# PiOBD_CM4_OBD_STN2100.net
KiCad netlist of a schematic drawn in Altium Designer
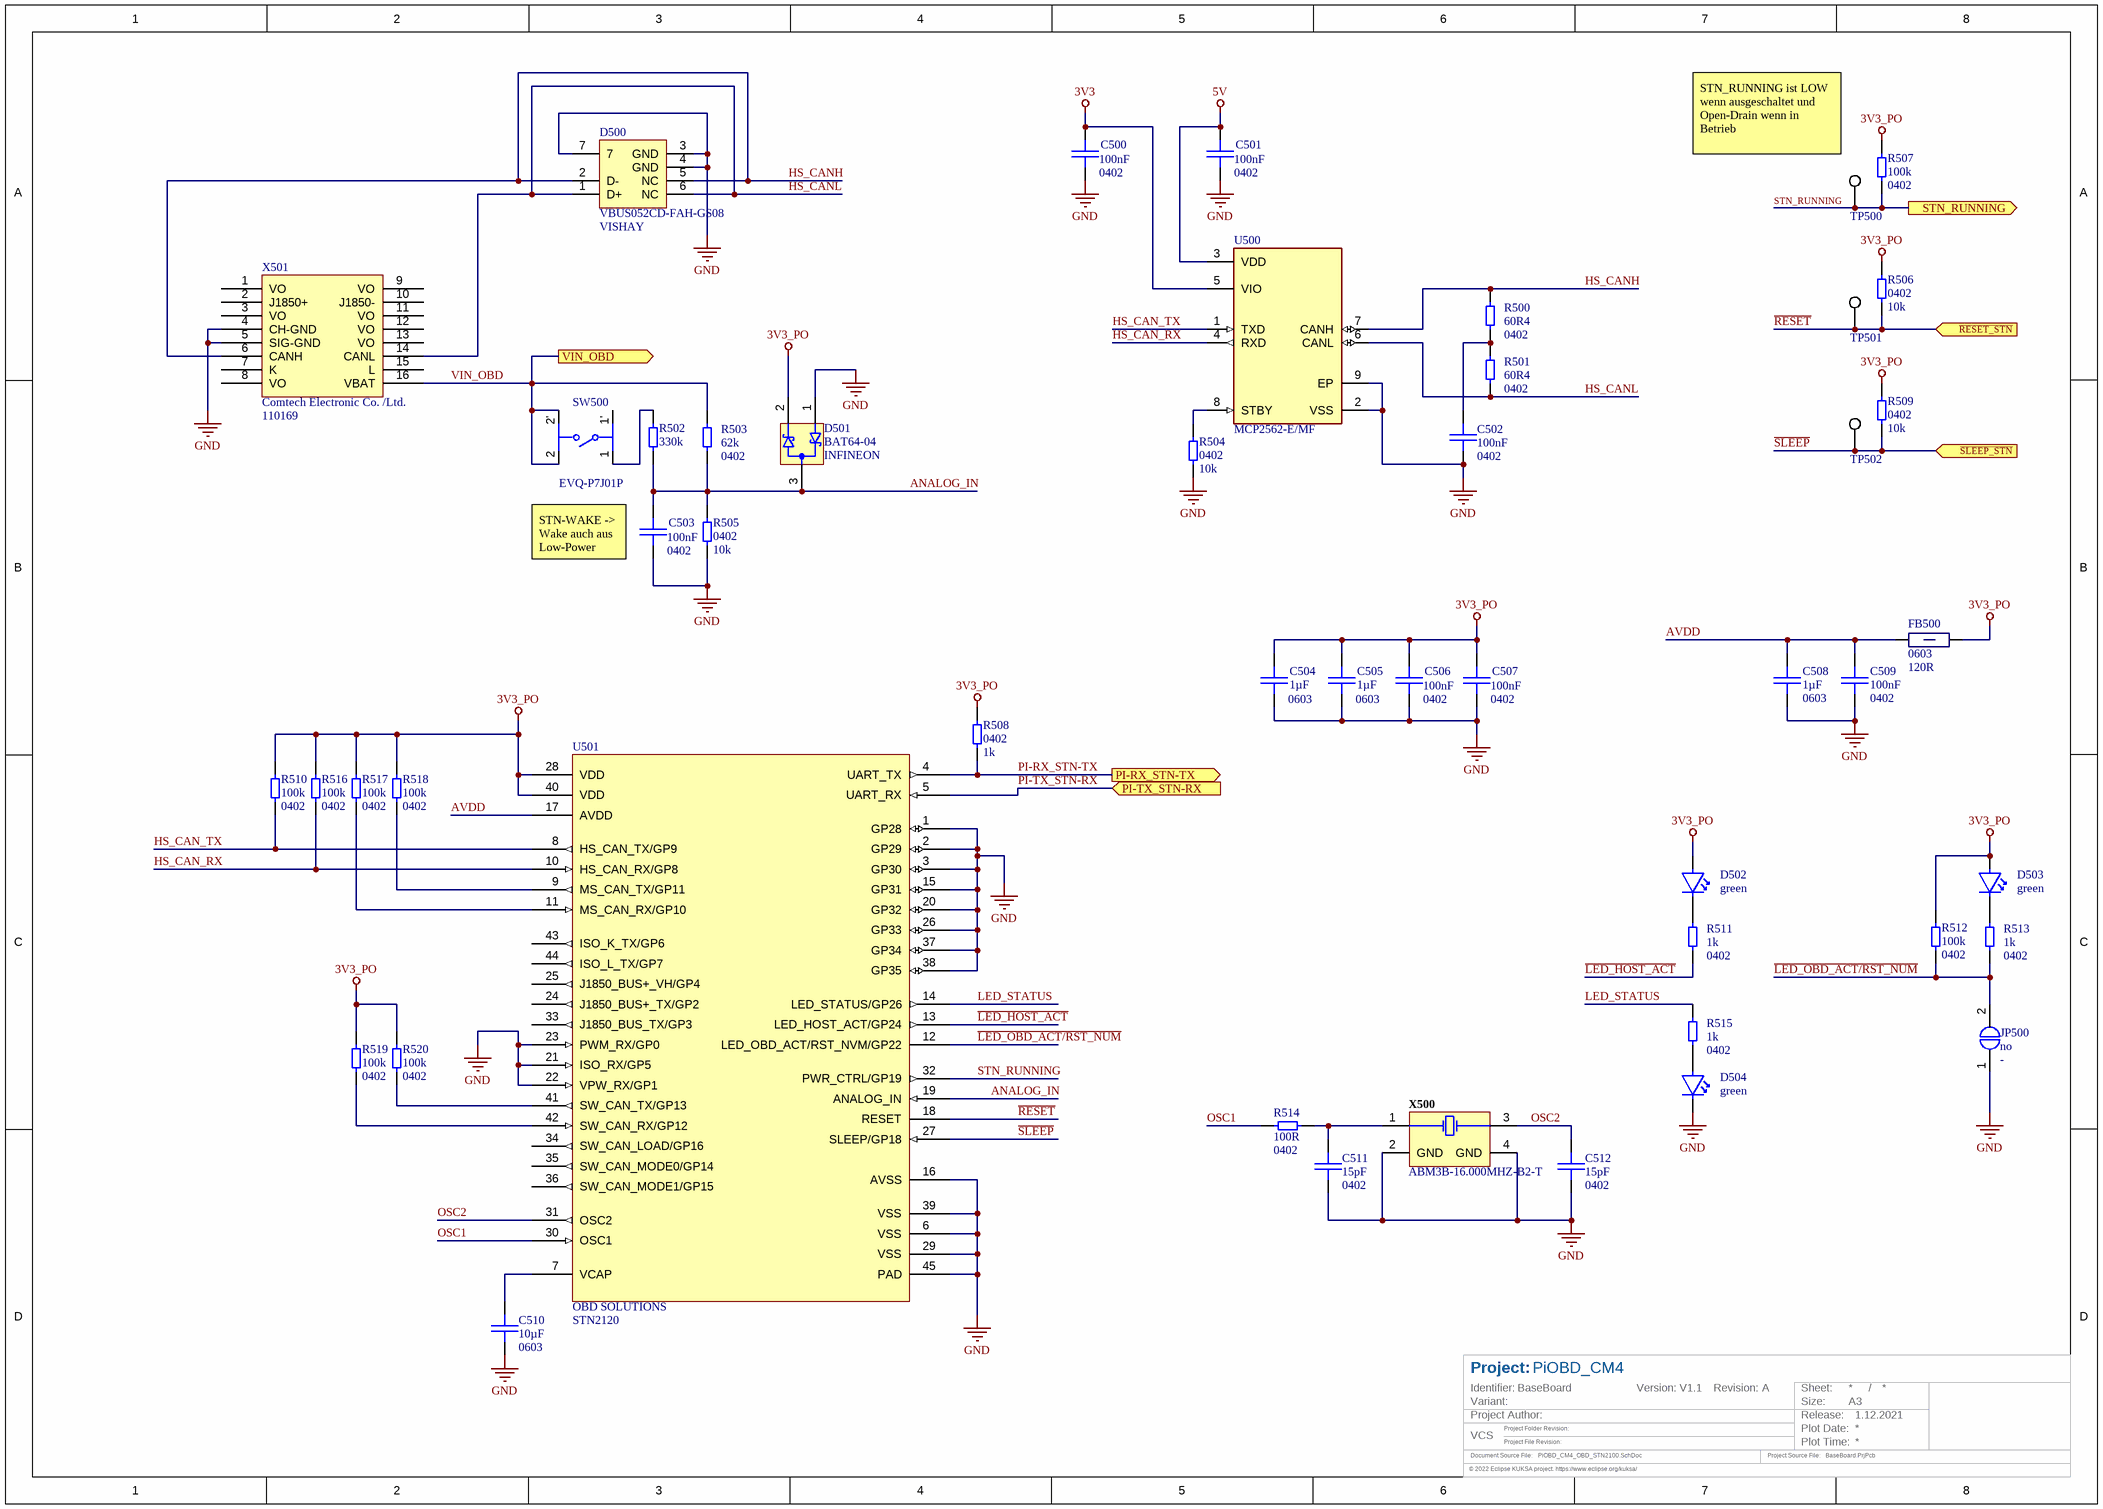
[diagram p0: PiOBD_CM4_OBD_STN2100.SchDoc]

(export (version "E")
  (design (tool "Eeschema 10.0.6"))
  (components
    (comp (ref "C500")
      (value "CAP 0402 100n -10% +10% 6.3V X7R")
      (footprint "CAP 0402 [1005 Metric] X050 N")
      (description "SMD/SMT 0402 6.3V -10% +10% X7R - Multilayer Ceramic Capacitors MLCC")
      (fields
        (field (name "MANUFACTURER") "MURATA")
        (field (name "CAPACITANCE") "100nF")
        (field (name "MANUFACTURER PART NUMBER") "GRM155R70J104KA01#")
        (field (name "CASE") "0402")
      )
      (libsource (lib "ShareLib") (part "Capacitor non-polarized - Standard Schematic"))
    )
    (comp (ref "C501")
      (value "CAP 0402 100n -10% +10% 6.3V X7R")
      (footprint "CAP 0402 [1005 Metric] X050 N")
      (description "SMD/SMT 0402 6.3V -10% +10% X7R - Multilayer Ceramic Capacitors MLCC")
      (fields
        (field (name "MANUFACTURER") "MURATA")
        (field (name "CAPACITANCE") "100nF")
        (field (name "MANUFACTURER PART NUMBER") "GRM155R70J104KA01#")
        (field (name "CASE") "0402")
      )
      (libsource (lib "ShareLib") (part "Capacitor non-polarized - Standard Schematic"))
    )
    (comp (ref "C502")
      (value "CAP 0402 100n -10% +10% 6.3V X7R")
      (footprint "CAP 0402 [1005 Metric] X050 N")
      (description "SMD/SMT 0402 6.3V -10% +10% X7R - Multilayer Ceramic Capacitors MLCC")
      (fields
        (field (name "MANUFACTURER") "MURATA")
        (field (name "CAPACITANCE") "100nF")
        (field (name "MANUFACTURER PART NUMBER") "GRM155R70J104KA01#")
        (field (name "CASE") "0402")
      )
      (libsource (lib "ShareLib") (part "Capacitor non-polarized - Standard Schematic"))
    )
    (comp (ref "C503")
      (value "CAP 0402 100n -10% +10% 6.3V X7R")
      (footprint "CAP 0402 [1005 Metric] X050 N")
      (description "SMD/SMT 0402 6.3V -10% +10% X7R - Multilayer Ceramic Capacitors MLCC")
      (fields
        (field (name "MANUFACTURER") "MURATA")
        (field (name "CAPACITANCE") "100nF")
        (field (name "MANUFACTURER PART NUMBER") "GRM155R70J104KA01#")
        (field (name "CASE") "0402")
      )
      (libsource (lib "ShareLib") (part "Capacitor non-polarized - Standard Schematic"))
    )
    (comp (ref "C504")
      (value "CAP 0603 1u -10% +10% 10V X7R")
      (footprint "CAP 0603 [1608 Metric] X080 N")
      (description "SMD/SMT 0603 10V -10% +10% X7R - Multilayer Ceramic Capacitors MLCC")
      (fields
        (field (name "CAPACITANCE") "1µF")
        (field (name "MANUFACTURER PART NUMBER") "GRM188R71A105KA61#")
        (field (name "MANUFACTURER") "MURATA")
        (field (name "CASE") "0603")
      )
      (libsource (lib "ShareLib") (part "Capacitor non-polarized - Standard Schematic"))
    )
    (comp (ref "C505")
      (value "CAP 0603 1u -10% +10% 10V X7R")
      (footprint "CAP 0603 [1608 Metric] X080 N")
      (description "SMD/SMT 0603 10V -10% +10% X7R - Multilayer Ceramic Capacitors MLCC")
      (fields
        (field (name "CAPACITANCE") "1µF")
        (field (name "MANUFACTURER PART NUMBER") "GRM188R71A105KA61#")
        (field (name "MANUFACTURER") "MURATA")
        (field (name "CASE") "0603")
      )
      (libsource (lib "ShareLib") (part "Capacitor non-polarized - Standard Schematic"))
    )
    (comp (ref "C506")
      (value "CAP 0402 100n -10% +10% 6.3V X7R")
      (footprint "CAP 0402 [1005 Metric] X050 N")
      (description "SMD/SMT 0402 6.3V -10% +10% X7R - Multilayer Ceramic Capacitors MLCC")
      (fields
        (field (name "MANUFACTURER") "MURATA")
        (field (name "CAPACITANCE") "100nF")
        (field (name "MANUFACTURER PART NUMBER") "GRM155R70J104KA01#")
        (field (name "CASE") "0402")
      )
      (libsource (lib "ShareLib") (part "Capacitor non-polarized - Standard Schematic"))
    )
    (comp (ref "C507")
      (value "CAP 0402 100n -10% +10% 6.3V X7R")
      (footprint "CAP 0402 [1005 Metric] X050 N")
      (description "SMD/SMT 0402 6.3V -10% +10% X7R - Multilayer Ceramic Capacitors MLCC")
      (fields
        (field (name "MANUFACTURER") "MURATA")
        (field (name "CAPACITANCE") "100nF")
        (field (name "MANUFACTURER PART NUMBER") "GRM155R70J104KA01#")
        (field (name "CASE") "0402")
      )
      (libsource (lib "ShareLib") (part "Capacitor non-polarized - Standard Schematic"))
    )
    (comp (ref "C508")
      (value "CAP 0603 1u -10% +10% 10V X7R")
      (footprint "CAP 0603 [1608 Metric] X080 N")
      (description "SMD/SMT 0603 10V -10% +10% X7R - Multilayer Ceramic Capacitors MLCC")
      (fields
        (field (name "CAPACITANCE") "1µF")
        (field (name "MANUFACTURER PART NUMBER") "GRM188R71A105KA61#")
        (field (name "MANUFACTURER") "MURATA")
        (field (name "CASE") "0603")
      )
      (libsource (lib "ShareLib") (part "Capacitor non-polarized - Standard Schematic"))
    )
    (comp (ref "C509")
      (value "CAP 0402 100n -10% +10% 6.3V X7R")
      (footprint "CAP 0402 [1005 Metric] X050 N")
      (description "SMD/SMT 0402 6.3V -10% +10% X7R - Multilayer Ceramic Capacitors MLCC")
      (fields
        (field (name "MANUFACTURER") "MURATA")
        (field (name "CAPACITANCE") "100nF")
        (field (name "MANUFACTURER PART NUMBER") "GRM155R70J104KA01#")
        (field (name "CASE") "0402")
      )
      (libsource (lib "ShareLib") (part "Capacitor non-polarized - Standard Schematic"))
    )
    (comp (ref "C510")
      (value "CAP 0603 10µF -20% +20% 6.3V X5R")
      (footprint "CAP 0603 [1608 Metric] X080 N")
      (description "SMT 10µF ±20% 6,3 V Keramikkondensatoren X5R")
      (fields
        (field (name "MANUFACTURER PART NUMBER") "GRM188R60J106ME84")
        (field (name "CAPACITANCE") "10µF")
        (field (name "MANUFACTURER") "MURATA")
        (field (name "CASE") "0603")
      )
      (libsource (lib "ShareLib") (part "Capacitor non-polarized - Standard Schematic"))
    )
    (comp (ref "C511")
      (value "CAP 0402 15p -2% +2% 25V C0G")
      (footprint "CAP 0402 [1005 Metric] X050 N")
      (description "SMD/SMT 0402 25V -2% +2% C0G - Multilayer Ceramic Capacitors MLCC")
      (fields
        (field (name "MANUFACTURER") "MURATA")
        (field (name "MANUFACTURER PART NUMBER") "GRM1555C1E150GA01#")
        (field (name "CASE") "0402")
        (field (name "CAPACITANCE") "15pF")
      )
      (libsource (lib "ShareLib") (part "Capacitor non-polarized - Standard Schematic"))
    )
    (comp (ref "C512")
      (value "CAP 0402 15p -2% +2% 25V C0G")
      (footprint "CAP 0402 [1005 Metric] X050 N")
      (description "SMD/SMT 0402 25V -2% +2% C0G - Multilayer Ceramic Capacitors MLCC")
      (fields
        (field (name "MANUFACTURER") "MURATA")
        (field (name "MANUFACTURER PART NUMBER") "GRM1555C1E150GA01#")
        (field (name "CASE") "0402")
        (field (name "CAPACITANCE") "15pF")
      )
      (libsource (lib "ShareLib") (part "Capacitor non-polarized - Standard Schematic"))
    )
    (comp (ref "D500")
      (value "VISHAY - VBUS052CD-FAH-GS08")
      (footprint "VISHAY - VBUS052CD-FAH")
      (description "2-Line BUS-Port ESD-Protection - Flow Through Design")
      (fields
        (field (name "MANUFACTURER PART NUMBER") "VBUS052CD-FAH-GS08")
        (field (name "MANUFACTURER") "VISHAY")
      )
      (libsource (lib "ShareLib") (part "VISHAY - VBUS052CD-FAH"))
    )
    (comp (ref "D501")
      (value "INFINEON - BAT64-04")
      (footprint "INFINEON - BAT64-04")
      (description "Dual Silicon Schottky Diodes in series configuration")
      (fields (field (name "MANUFACTURER PART NUMBER") "BAT64-04") (field (name "MANUFACTURER") "INFINEON"))
      (libsource (lib "ShareLib") (part "Dual Series Schottky Diode"))
    )
    (comp (ref "D502")
      (value "WUERTH ELEKTRONIK - 155124VS73200")
      (footprint "WUERTH ELEKTRONIK - WL-SMSW")
      (description "LED, GREEN, Right Angle SMD 3.2*1.0mm WL-SMSW SMT Mono-color Side view Waterclear")
      (fields
        (field (name "COLOUR LED1") "green")
        (field (name "MANUFACTURER") "WUERTH ELEKTRONIK")
        (field (name "MANUFACTURER PART NUMBER") "155124VS73200")
      )
      (libsource (lib "ShareLib") (part "LED - Standard Schematic"))
    )
    (comp (ref "D503")
      (value "WUERTH ELEKTRONIK - 155124VS73200")
      (footprint "WUERTH ELEKTRONIK - WL-SMSW")
      (description "LED, GREEN, Right Angle SMD 3.2*1.0mm WL-SMSW SMT Mono-color Side view Waterclear")
      (fields
        (field (name "COLOUR LED1") "green")
        (field (name "MANUFACTURER") "WUERTH ELEKTRONIK")
        (field (name "MANUFACTURER PART NUMBER") "155124VS73200")
      )
      (libsource (lib "ShareLib") (part "LED - Standard Schematic"))
    )
    (comp (ref "D504")
      (value "WUERTH ELEKTRONIK - 155124VS73200")
      (footprint "WUERTH ELEKTRONIK - WL-SMSW")
      (description "LED, GREEN, Right Angle SMD 3.2*1.0mm WL-SMSW SMT Mono-color Side view Waterclear")
      (fields
        (field (name "COLOUR LED1") "green")
        (field (name "MANUFACTURER") "WUERTH ELEKTRONIK")
        (field (name "MANUFACTURER PART NUMBER") "155124VS73200")
      )
      (libsource (lib "ShareLib") (part "LED - Standard Schematic"))
    )
    (comp (ref "FB500")
      (value "MURATA - BLM18AG121SN1D")
      (footprint "Ferrite Beads 0603 (1608 Metric)")
      (description "120 Ohms @ 100MHz 1 Power Line Ferrite Bead 0603 (1608 Metric) 800mA 180mOhm")
      (fields
        (field (name "CASE") "0603")
        (field (name "IMPEDANCE") "120R")
        (field (name "MANUFACTURER") "MURATA")
        (field (name "MANUFACTURER PART NUMBER") "BLM18AG121SN1D")
      )
      (libsource (lib "ShareLib") (part "MURATA - BLM18PG471SN1"))
    )
    (comp (ref "JP500")
      (value "Solder Jumper 0402 unbestückt")
      (footprint "Solder Jumper 0402 unbestückt")
      (fields (field (name "ASSEMBLY") "no") (field (name "CASE") "-"))
      (libsource (lib "ShareLib") (part "Solder Jumper"))
    )
    (comp (ref "R500")
      (value "RES 0402 60R4 1% 0W0625")
      (footprint "RES 0402 [1005 Metric]_N")
      (description "RC0402 series chip resistor with lead-free terminations made by thick film process")
      (fields
        (field (name "RESISTANCE") "60R4")
        (field (name "MANUFACTURER PART NUMBER") "RC0402FR-0760R4L")
        (field (name "MANUFACTURER") "YAGEO")
        (field (name "CASE") "0402")
      )
      (libsource (lib "ShareLib") (part "Standard Schematic - Resistor Universal"))
    )
    (comp (ref "R501")
      (value "RES 0402 60R4 1% 0W0625")
      (footprint "RES 0402 [1005 Metric]_N")
      (description "RC0402 series chip resistor with lead-free terminations made by thick film process")
      (fields
        (field (name "RESISTANCE") "60R4")
        (field (name "MANUFACTURER PART NUMBER") "RC0402FR-0760R4L")
        (field (name "MANUFACTURER") "YAGEO")
        (field (name "CASE") "0402")
      )
      (libsource (lib "ShareLib") (part "Standard Schematic - Resistor Universal"))
    )
    (comp (ref "R502")
      (value "RES 0402 330K 1% 0W0625")
      (footprint "RES 0402 [1005 Metric]_N")
      (description "RC0402 series chip resistor with lead-free terminations made by thick film process")
      (fields
        (field (name "MANUFACTURER PART NUMBER") "RC0402FR-07330KL")
        (field (name "MANUFACTURER") "YAGEO")
        (field (name "RESISTANCE") "330k")
      )
      (libsource (lib "ShareLib") (part "Standard Schematic - Resistor Universal"))
    )
    (comp (ref "R503")
      (value "RES 0402 62K 1% 0W0625")
      (footprint "RES 0402 [1005 Metric]_N")
      (description "RC0402 series chip resistor with lead-free terminations made by thick film process")
      (fields
        (field (name "MANUFACTURER PART NUMBER") "RC0402FR-0762KL")
        (field (name "RESISTANCE") "62k")
        (field (name "MANUFACTURER") "YAGEO")
        (field (name "CASE") "0402")
      )
      (libsource (lib "ShareLib") (part "Standard Schematic - Resistor Universal"))
    )
    (comp (ref "R504")
      (value "RES 0402 10K 1% 0W0625")
      (footprint "RES 0402 [1005 Metric]_N")
      (description "RC0402 series chip resistor with lead-free terminations made by thick film process")
      (fields
        (field (name "MANUFACTURER PART NUMBER") "RC0402FR-0710KL")
        (field (name "CASE") "0402")
        (field (name "MANUFACTURER") "YAGEO")
        (field (name "RESISTANCE") "10k")
      )
      (libsource (lib "ShareLib") (part "Standard Schematic - Resistor Universal"))
    )
    (comp (ref "R505")
      (value "RES 0402 10K 1% 0W0625")
      (footprint "RES 0402 [1005 Metric]_N")
      (description "RC0402 series chip resistor with lead-free terminations made by thick film process")
      (fields
        (field (name "MANUFACTURER PART NUMBER") "RC0402FR-0710KL")
        (field (name "CASE") "0402")
        (field (name "MANUFACTURER") "YAGEO")
        (field (name "RESISTANCE") "10k")
      )
      (libsource (lib "ShareLib") (part "Standard Schematic - Resistor Universal"))
    )
    (comp (ref "R506")
      (value "RES 0402 10K 1% 0W0625")
      (footprint "RES 0402 [1005 Metric]_N")
      (description "RC0402 series chip resistor with lead-free terminations made by thick film process")
      (fields
        (field (name "MANUFACTURER PART NUMBER") "RC0402FR-0710KL")
        (field (name "CASE") "0402")
        (field (name "MANUFACTURER") "YAGEO")
        (field (name "RESISTANCE") "10k")
      )
      (libsource (lib "ShareLib") (part "Standard Schematic - Resistor Universal"))
    )
    (comp (ref "R507")
      (value "RES 0402 100K 1% 0W0625")
      (footprint "RES 0402 [1005 Metric]_N")
      (description "RC0402 series chip resistor with lead-free terminations made by thick film process")
      (fields
        (field (name "RESISTANCE") "100k")
        (field (name "MANUFACTURER PART NUMBER") "RC0402FR-07100KL")
        (field (name "CASE") "0402")
        (field (name "MANUFACTURER") "YAGEO")
      )
      (libsource (lib "ShareLib") (part "Standard Schematic - Resistor Universal"))
    )
    (comp (ref "R508")
      (value "RES 0402 1K 1% 0W0625")
      (footprint "RES 0402 [1005 Metric]_N")
      (description "RC0402 series chip resistor with lead-free terminations made by thick film process")
      (fields
        (field (name "CASE") "0402")
        (field (name "MANUFACTURER PART NUMBER") "RC0402FR-071KL")
        (field (name "MANUFACTURER") "YAGEO")
        (field (name "RESISTANCE") "1k")
      )
      (libsource (lib "ShareLib") (part "Standard Schematic - Resistor Universal"))
    )
    (comp (ref "R509")
      (value "RES 0402 10K 1% 0W0625")
      (footprint "RES 0402 [1005 Metric]_N")
      (description "RC0402 series chip resistor with lead-free terminations made by thick film process")
      (fields
        (field (name "MANUFACTURER PART NUMBER") "RC0402FR-0710KL")
        (field (name "CASE") "0402")
        (field (name "MANUFACTURER") "YAGEO")
        (field (name "RESISTANCE") "10k")
      )
      (libsource (lib "ShareLib") (part "Standard Schematic - Resistor Universal"))
    )
    (comp (ref "R510")
      (value "RES 0402 100K 1% 0W0625")
      (footprint "RES 0402 [1005 Metric]_N")
      (description "RC0402 series chip resistor with lead-free terminations made by thick film process")
      (fields
        (field (name "RESISTANCE") "100k")
        (field (name "MANUFACTURER PART NUMBER") "RC0402FR-07100KL")
        (field (name "CASE") "0402")
        (field (name "MANUFACTURER") "YAGEO")
      )
      (libsource (lib "ShareLib") (part "Standard Schematic - Resistor Universal"))
    )
    (comp (ref "R511")
      (value "RES 0402 1K 1% 0W0625")
      (footprint "RES 0402 [1005 Metric]_N")
      (description "RC0402 series chip resistor with lead-free terminations made by thick film process")
      (fields
        (field (name "CASE") "0402")
        (field (name "MANUFACTURER PART NUMBER") "RC0402FR-071KL")
        (field (name "MANUFACTURER") "YAGEO")
        (field (name "RESISTANCE") "1k")
      )
      (libsource (lib "ShareLib") (part "Standard Schematic - Resistor Universal"))
    )
    (comp (ref "R512")
      (value "RES 0402 100K 1% 0W0625")
      (footprint "RES 0402 [1005 Metric]_N")
      (description "RC0402 series chip resistor with lead-free terminations made by thick film process")
      (fields
        (field (name "RESISTANCE") "100k")
        (field (name "MANUFACTURER PART NUMBER") "RC0402FR-07100KL")
        (field (name "CASE") "0402")
        (field (name "MANUFACTURER") "YAGEO")
      )
      (libsource (lib "ShareLib") (part "Standard Schematic - Resistor Universal"))
    )
    (comp (ref "R513")
      (value "RES 0402 1K 1% 0W0625")
      (footprint "RES 0402 [1005 Metric]_N")
      (description "RC0402 series chip resistor with lead-free terminations made by thick film process")
      (fields
        (field (name "CASE") "0402")
        (field (name "MANUFACTURER PART NUMBER") "RC0402FR-071KL")
        (field (name "MANUFACTURER") "YAGEO")
        (field (name "RESISTANCE") "1k")
      )
      (libsource (lib "ShareLib") (part "Standard Schematic - Resistor Universal"))
    )
    (comp (ref "R514")
      (value "RES 0402 100R 1% 63mW")
      (footprint "RES 0402 [1005 Metric]_N")
      (description "RC0402 series chip resistor with lead-free terminations made by thick film process")
      (fields
        (field (name "RESISTANCE") "100R")
        (field (name "CASE") "0402")
        (field (name "MANUFACTURER") "ROHM")
        (field (name "MANUFACTURER PART NUMBER") "MCR01MZPF100")
      )
      (libsource (lib "ShareLib") (part "Standard Schematic - Resistor Universal"))
    )
    (comp (ref "R515")
      (value "RES 0402 1K 1% 0W0625")
      (footprint "RES 0402 [1005 Metric]_N")
      (description "RC0402 series chip resistor with lead-free terminations made by thick film process")
      (fields
        (field (name "CASE") "0402")
        (field (name "MANUFACTURER PART NUMBER") "RC0402FR-071KL")
        (field (name "MANUFACTURER") "YAGEO")
        (field (name "RESISTANCE") "1k")
      )
      (libsource (lib "ShareLib") (part "Standard Schematic - Resistor Universal"))
    )
    (comp (ref "R516")
      (value "RES 0402 100K 1% 0W0625")
      (footprint "RES 0402 [1005 Metric]_N")
      (description "RC0402 series chip resistor with lead-free terminations made by thick film process")
      (fields
        (field (name "RESISTANCE") "100k")
        (field (name "MANUFACTURER PART NUMBER") "RC0402FR-07100KL")
        (field (name "CASE") "0402")
        (field (name "MANUFACTURER") "YAGEO")
      )
      (libsource (lib "ShareLib") (part "Standard Schematic - Resistor Universal"))
    )
    (comp (ref "R517")
      (value "RES 0402 100K 1% 0W0625")
      (footprint "RES 0402 [1005 Metric]_N")
      (description "RC0402 series chip resistor with lead-free terminations made by thick film process")
      (fields
        (field (name "RESISTANCE") "100k")
        (field (name "MANUFACTURER PART NUMBER") "RC0402FR-07100KL")
        (field (name "CASE") "0402")
        (field (name "MANUFACTURER") "YAGEO")
      )
      (libsource (lib "ShareLib") (part "Standard Schematic - Resistor Universal"))
    )
    (comp (ref "R518")
      (value "RES 0402 100K 1% 0W0625")
      (footprint "RES 0402 [1005 Metric]_N")
      (description "RC0402 series chip resistor with lead-free terminations made by thick film process")
      (fields
        (field (name "RESISTANCE") "100k")
        (field (name "MANUFACTURER PART NUMBER") "RC0402FR-07100KL")
        (field (name "CASE") "0402")
        (field (name "MANUFACTURER") "YAGEO")
      )
      (libsource (lib "ShareLib") (part "Standard Schematic - Resistor Universal"))
    )
    (comp (ref "R519")
      (value "RES 0402 100K 1% 0W0625")
      (footprint "RES 0402 [1005 Metric]_N")
      (description "RC0402 series chip resistor with lead-free terminations made by thick film process")
      (fields
        (field (name "RESISTANCE") "100k")
        (field (name "MANUFACTURER PART NUMBER") "RC0402FR-07100KL")
        (field (name "CASE") "0402")
        (field (name "MANUFACTURER") "YAGEO")
      )
      (libsource (lib "ShareLib") (part "Standard Schematic - Resistor Universal"))
    )
    (comp (ref "R520")
      (value "RES 0402 100K 1% 0W0625")
      (footprint "RES 0402 [1005 Metric]_N")
      (description "RC0402 series chip resistor with lead-free terminations made by thick film process")
      (fields
        (field (name "RESISTANCE") "100k")
        (field (name "MANUFACTURER PART NUMBER") "RC0402FR-07100KL")
        (field (name "CASE") "0402")
        (field (name "MANUFACTURER") "YAGEO")
      )
      (libsource (lib "ShareLib") (part "Standard Schematic - Resistor Universal"))
    )
    (comp (ref "SW500")
      (value "EVQ-P7J01P")
      (footprint "FP-EVQ-P7J01P-MFG")
      (description "SWITCH TACTILE SPST-NO 0.05A 12V")
      (fields
        (field (name "MANUFACTURER") "Panasonic")
        (field (name "OCTOPART") "https://octopart.com/evq-p7j01p-panasonic-29917078")
      )
      (libsource (lib "Altium Content Vault") (part "81ddb76e3b1ae09a591072546e26dfd"))
    )
    (comp (ref "TP500")
      (value "Testpad, 0.8mm x 0.8mm, round")
      (footprint "Testpad, 0.8mm x 0.8mm, round")
      (libsource (lib "ShareLib") (part "Testpoint (No BOM)"))
    )
    (comp (ref "TP501")
      (value "Testpad, 0.8mm x 0.8mm, round")
      (footprint "Testpad, 0.8mm x 0.8mm, round")
      (libsource (lib "ShareLib") (part "Testpoint (No BOM)"))
    )
    (comp (ref "TP502")
      (value "Testpad, 0.8mm x 0.8mm, round")
      (footprint "Testpad, 0.8mm x 0.8mm, round")
      (libsource (lib "ShareLib") (part "Testpoint (No BOM)"))
    )
    (comp (ref "U500")
      (value "MCP2562-E/MF")
      (footprint "FP-C04-062-MFG")
      (description "IC TRANSCEIVER HALF 1/1 8DFN")
      (fields
        (field (name "OCTOPART") "https://octopart.com/mcp2562-e%2Fmf-microchip-28494619")
        (field (name "MANUFACTURER") "Microchip Technology")
      )
      (libsource (lib "Altium Content Vault") (part "02f17a9452f5565b4e0dbded7188508"))
    )
    (comp (ref "U501")
      (value "OBD SOLUTIONS - STN2120")
      (footprint "QFN65P800X800X100_HS-45N")
      (fields
        (field (name "MANUFACTURER") "OBD SOLUTIONS")
        (field (name "MANUFACTURER PART NUMBER") "STN2120")
      )
      (libsource (lib "ShareLib") (part "STN2120"))
    )
    (comp (ref "X500")
      (value "ABM3B-16.000MHZ-B2-T")
      (footprint "ABRA-ABM3B-4_V")
      (description "Ceramic SMD Crystal, 16 MHz, +/- 20 ppm, 50 Ohm, -20 to 70 degC, 4-Pin SMD, RoHS, Tape and Reel")
      (fields (field (name "TOLERANCE") "30%"))
      (libsource (lib "Altium Content Vault") (part "XTAL-1-3-4"))
    )
    (comp (ref "X501")
      (value "COMTECH ELECTRONIC - OBD-2 Stiftblock")
      (footprint "COMTECH ELECTRONIC - OBD-2 Stiftblock-Footprint-1")
      (description "OBD-2 Stiftblock männlich PCB TH PKW Typ A")
      (fields
        (field (name "MANUFACTURER") "Comtech Electronic Co. /Ltd.")
        (field (name "MANUFACTURER PART NUMBER") "110169")
      )
      (libsource (lib "ShareLib") (part "COMTECH ELECTRONIC - OBD-2 Stiftblock"))
    )
  )
  (nets
    (net (code "1") (name "/ANALOG_IN") (class "Default")
      (node (ref "C503") (pin "2") (pinfunction "2_2") (pintype "passive"))
      (node (ref "D501") (pin "3") (pinfunction "3_3") (pintype "passive"))
      (node (ref "R502") (pin "1") (pinfunction "1_1") (pintype "passive"))
      (node (ref "R503") (pin "1") (pinfunction "1_1") (pintype "passive"))
      (node (ref "R505") (pin "1") (pinfunction "1_1") (pintype "passive"))
      (node (ref "U501") (pin "19") (pinfunction "ANALOG_IN_19") (pintype "input"))
    )
    (net (code "2") (name "/AVDD") (class "Default")
      (node (ref "C508") (pin "1") (pinfunction "1_1") (pintype "passive"))
      (node (ref "C509") (pin "2") (pinfunction "2_2") (pintype "passive"))
      (node (ref "FB500") (pin "2") (pinfunction "2_2") (pintype "passive"))
      (node (ref "U501") (pin "17") (pinfunction "AVDD_17") (pintype "passive"))
    )
    (net (code "3") (name "/HS_CANH") (class "Default")
      (node (ref "D500") (pin "2") (pinfunction "D-_2") (pintype "passive"))
      (node (ref "D500") (pin "5") (pinfunction "NC_5") (pintype "passive"))
      (node (ref "R500") (pin "2") (pinfunction "2_2") (pintype "passive"))
      (node (ref "U500") (pin "7") (pinfunction "CANH_7") (pintype "bidirectional"))
      (node (ref "X501") (pin "6") (pinfunction "CANH_6") (pintype "passive"))
    )
    (net (code "4") (name "/HS_CANL") (class "Default")
      (node (ref "D500") (pin "1") (pinfunction "D+_1") (pintype "passive"))
      (node (ref "D500") (pin "6") (pinfunction "NC_6") (pintype "passive"))
      (node (ref "R501") (pin "1") (pinfunction "1_1") (pintype "passive"))
      (node (ref "U500") (pin "6") (pinfunction "CANL_6") (pintype "bidirectional"))
      (node (ref "X501") (pin "14") (pinfunction "CANL_14") (pintype "passive"))
    )
    (net (code "5") (name "/HS_CAN_RX") (class "Default")
      (node (ref "R516") (pin "1") (pinfunction "1_1") (pintype "passive"))
      (node (ref "U500") (pin "4") (pinfunction "RXD_4") (pintype "output"))
      (node (ref "U501") (pin "10") (pinfunction "HS_CAN_RX/GP8_10") (pintype "input"))
    )
    (net (code "6") (name "/HS_CAN_TX") (class "Default")
      (node (ref "R510") (pin "1") (pinfunction "1_1") (pintype "passive"))
      (node (ref "U500") (pin "1") (pinfunction "TXD_1") (pintype "input"))
      (node (ref "U501") (pin "8") (pinfunction "HS_CAN_TX/GP9_8") (pintype "output"))
    )
    (net (code "7") (name "/LED_HOST_ACT") (class "Default")
      (node (ref "R511") (pin "1") (pinfunction "1_1") (pintype "passive"))
      (node (ref "U501") (pin "13") (pinfunction "LED_HOST_ACT/GP24_13") (pintype "output"))
    )
    (net (code "8") (name "/LED_OBD_ACT{slash}RST_NUM") (class "Default")
      (node (ref "JP500") (pin "2") (pinfunction "2_2") (pintype "passive"))
      (node (ref "R512") (pin "1") (pinfunction "1_1") (pintype "passive"))
      (node (ref "R513") (pin "1") (pinfunction "1_1") (pintype "passive"))
      (node (ref "U501") (pin "12") (pinfunction "LED_OBD_ACT/RST_NVM/GP22_12") (pintype "passive"))
    )
    (net (code "9") (name "/LED_STATUS") (class "Default")
      (node (ref "R515") (pin "2") (pinfunction "2_2") (pintype "passive"))
      (node (ref "U501") (pin "14") (pinfunction "LED_STATUS/GP26_14") (pintype "output"))
    )
    (net (code "10") (name "/OSC1") (class "Default")
      (node (ref "R514") (pin "1") (pinfunction "1_1") (pintype "passive"))
      (node (ref "U501") (pin "30") (pinfunction "OSC1_30") (pintype "input"))
    )
    (net (code "11") (name "/OSC2") (class "Default")
      (node (ref "C512") (pin "2") (pinfunction "2_2") (pintype "passive"))
      (node (ref "U501") (pin "31") (pinfunction "OSC2_31") (pintype "output"))
      (node (ref "X500") (pin "3") (pinfunction "X2_3") (pintype "passive"))
    )
    (net (code "12") (name "/PI-RX_STN-TX") (class "Default")
      (node (ref "R508") (pin "1") (pinfunction "1_1") (pintype "passive"))
      (node (ref "U501") (pin "4") (pinfunction "UART_TX_4") (pintype "output"))
    )
    (net (code "13") (name "/PI-TX_STN-RX") (class "Default")
      (node (ref "U501") (pin "5") (pinfunction "UART_RX_5") (pintype "input"))
    )
    (net (code "14") (name "/RESET") (class "Default")
      (node (ref "R506") (pin "2") (pinfunction "2_2") (pintype "passive"))
      (node (ref "TP501") (pin "1") (pinfunction "1_1") (pintype "passive"))
      (node (ref "U501") (pin "18") (pinfunction "RESET_18") (pintype "passive"))
    )
    (net (code "15") (name "/SLEEP") (class "Default")
      (node (ref "R509") (pin "2") (pinfunction "2_2") (pintype "passive"))
      (node (ref "TP502") (pin "1") (pinfunction "1_1") (pintype "passive"))
      (node (ref "U501") (pin "27") (pinfunction "SLEEP/GP18_27") (pintype "input"))
    )
    (net (code "16") (name "/STN_RUNNING") (class "Default")
      (node (ref "R507") (pin "1") (pinfunction "1_1") (pintype "passive"))
      (node (ref "TP500") (pin "1") (pinfunction "1_1") (pintype "passive"))
      (node (ref "U501") (pin "32") (pinfunction "PWR_CTRL/GP19_32") (pintype "output"))
    )
    (net (code "17") (name "/VIN_OBD") (class "Default")
      (node (ref "R503") (pin "2") (pinfunction "2_2") (pintype "passive"))
      (node (ref "SW500") (pin "2") (pinfunction "2_2") (pintype "passive"))
      (node (ref "SW500") (pin "2'") (pinfunction "2'_2'") (pintype "passive"))
      (node (ref "X501") (pin "16") (pinfunction "VBAT_16") (pintype "passive"))
    )
    (net (code "18") (name "3V3") (class "Default")
      (node (ref "C500") (pin "2") (pinfunction "2_2") (pintype "passive"))
      (node (ref "U500") (pin "5") (pinfunction "VIO_5") (pintype "power_in"))
    )
    (net (code "19") (name "3V3_PO") (class "Default")
      (node (ref "C504") (pin "1") (pinfunction "1_1") (pintype "passive"))
      (node (ref "C505") (pin "1") (pinfunction "1_1") (pintype "passive"))
      (node (ref "C506") (pin "2") (pinfunction "2_2") (pintype "passive"))
      (node (ref "C507") (pin "2") (pinfunction "2_2") (pintype "passive"))
      (node (ref "D501") (pin "2") (pinfunction "2_2") (pintype "passive"))
      (node (ref "D502") (pin "A") (pinfunction "A_A") (pintype "passive"))
      (node (ref "D503") (pin "A") (pinfunction "A_A") (pintype "passive"))
      (node (ref "FB500") (pin "1") (pinfunction "1_1") (pintype "passive"))
      (node (ref "R506") (pin "1") (pinfunction "1_1") (pintype "passive"))
      (node (ref "R507") (pin "2") (pinfunction "2_2") (pintype "passive"))
      (node (ref "R508") (pin "2") (pinfunction "2_2") (pintype "passive"))
      (node (ref "R509") (pin "1") (pinfunction "1_1") (pintype "passive"))
      (node (ref "R510") (pin "2") (pinfunction "2_2") (pintype "passive"))
      (node (ref "R512") (pin "2") (pinfunction "2_2") (pintype "passive"))
      (node (ref "R516") (pin "2") (pinfunction "2_2") (pintype "passive"))
      (node (ref "R517") (pin "2") (pinfunction "2_2") (pintype "passive"))
      (node (ref "R518") (pin "2") (pinfunction "2_2") (pintype "passive"))
      (node (ref "R519") (pin "2") (pinfunction "2_2") (pintype "passive"))
      (node (ref "R520") (pin "2") (pinfunction "2_2") (pintype "passive"))
      (node (ref "U501") (pin "28") (pinfunction "VDD_28") (pintype "passive"))
      (node (ref "U501") (pin "40") (pinfunction "VDD_40") (pintype "passive"))
    )
    (net (code "20") (name "5V") (class "Default")
      (node (ref "C501") (pin "2") (pinfunction "2_2") (pintype "passive"))
      (node (ref "U500") (pin "3") (pinfunction "VDD_3") (pintype "power_in"))
    )
    (net (code "21") (name "GND") (class "Default")
      (node (ref "C500") (pin "1") (pinfunction "1_1") (pintype "passive"))
      (node (ref "C501") (pin "1") (pinfunction "1_1") (pintype "passive"))
      (node (ref "C502") (pin "2") (pinfunction "2_2") (pintype "passive"))
      (node (ref "C503") (pin "1") (pinfunction "1_1") (pintype "passive"))
      (node (ref "C504") (pin "2") (pinfunction "2_2") (pintype "passive"))
      (node (ref "C505") (pin "2") (pinfunction "2_2") (pintype "passive"))
      (node (ref "C506") (pin "1") (pinfunction "1_1") (pintype "passive"))
      (node (ref "C507") (pin "1") (pinfunction "1_1") (pintype "passive"))
      (node (ref "C508") (pin "2") (pinfunction "2_2") (pintype "passive"))
      (node (ref "C509") (pin "1") (pinfunction "1_1") (pintype "passive"))
      (node (ref "C510") (pin "2") (pinfunction "2_2") (pintype "passive"))
      (node (ref "C511") (pin "1") (pinfunction "1_1") (pintype "passive"))
      (node (ref "C512") (pin "1") (pinfunction "1_1") (pintype "passive"))
      (node (ref "D500") (pin "3") (pinfunction "GND_3") (pintype "power_in"))
      (node (ref "D500") (pin "4") (pinfunction "GND_4") (pintype "power_in"))
      (node (ref "D500") (pin "7") (pinfunction "7_7") (pintype "passive"))
      (node (ref "D501") (pin "1") (pinfunction "1_1") (pintype "passive"))
      (node (ref "D504") (pin "C") (pinfunction "C_C") (pintype "passive"))
      (node (ref "JP500") (pin "1") (pinfunction "1_1") (pintype "passive"))
      (node (ref "R504") (pin "2") (pinfunction "2_2") (pintype "passive"))
      (node (ref "R505") (pin "2") (pinfunction "2_2") (pintype "passive"))
      (node (ref "U500") (pin "2") (pinfunction "VSS_2") (pintype "power_in"))
      (node (ref "U500") (pin "9") (pinfunction "EP_9") (pintype "power_in"))
      (node (ref "U501") (pin "1") (pinfunction "GP28_1") (pintype "bidirectional"))
      (node (ref "U501") (pin "15") (pinfunction "GP31_15") (pintype "bidirectional"))
      (node (ref "U501") (pin "16") (pinfunction "AVSS_16") (pintype "passive"))
      (node (ref "U501") (pin "2") (pinfunction "GP29_2") (pintype "bidirectional"))
      (node (ref "U501") (pin "20") (pinfunction "GP32_20") (pintype "bidirectional"))
      (node (ref "U501") (pin "21") (pinfunction "ISO_RX/GP5_21") (pintype "input"))
      (node (ref "U501") (pin "22") (pinfunction "VPW_RX/GP1_22") (pintype "input"))
      (node (ref "U501") (pin "23") (pinfunction "PWM_RX/GP0_23") (pintype "input"))
      (node (ref "U501") (pin "26") (pinfunction "GP33_26") (pintype "bidirectional"))
      (node (ref "U501") (pin "29") (pinfunction "VSS_29") (pintype "passive"))
      (node (ref "U501") (pin "3") (pinfunction "GP30_3") (pintype "bidirectional"))
      (node (ref "U501") (pin "37") (pinfunction "GP34_37") (pintype "bidirectional"))
      (node (ref "U501") (pin "38") (pinfunction "GP35_38") (pintype "bidirectional"))
      (node (ref "U501") (pin "39") (pinfunction "VSS_39") (pintype "passive"))
      (node (ref "U501") (pin "45") (pinfunction "PAD_45") (pintype "passive"))
      (node (ref "U501") (pin "6") (pinfunction "VSS_6") (pintype "passive"))
      (node (ref "X500") (pin "2") (pinfunction "GND_2") (pintype "power_in"))
      (node (ref "X500") (pin "4") (pinfunction "GND_4") (pintype "power_in"))
      (node (ref "X501") (pin "4") (pinfunction "CH-GND_4") (pintype "passive"))
      (node (ref "X501") (pin "5") (pinfunction "SIG-GND_5") (pintype "passive"))
    )
    (net (code "22") (name "Net-(C502-Pad1)") (class "Default")
      (node (ref "C502") (pin "1") (pinfunction "1_1") (pintype "passive"))
      (node (ref "R500") (pin "1") (pinfunction "1_1") (pintype "passive"))
      (node (ref "R501") (pin "2") (pinfunction "2_2") (pintype "passive"))
    )
    (net (code "23") (name "Net-(D502-PadC)") (class "Default")
      (node (ref "D502") (pin "C") (pinfunction "C_C") (pintype "passive"))
      (node (ref "R511") (pin "2") (pinfunction "2_2") (pintype "passive"))
    )
    (net (code "24") (name "Net-(D503-PadC)") (class "Default")
      (node (ref "D503") (pin "C") (pinfunction "C_C") (pintype "passive"))
      (node (ref "R513") (pin "2") (pinfunction "2_2") (pintype "passive"))
    )
    (net (code "25") (name "Net-(D504-PadA)") (class "Default")
      (node (ref "D504") (pin "A") (pinfunction "A_A") (pintype "passive"))
      (node (ref "R515") (pin "1") (pinfunction "1_1") (pintype "passive"))
    )
    (net (code "26") (name "Net-(R502-Pad2)") (class "Default")
      (node (ref "R502") (pin "2") (pinfunction "2_2") (pintype "passive"))
      (node (ref "SW500") (pin "1") (pinfunction "1_1") (pintype "passive"))
    )
    (net (code "27") (name "Net-(U500-STBY)") (class "Default")
      (node (ref "R504") (pin "1") (pinfunction "1_1") (pintype "passive"))
      (node (ref "U500") (pin "8") (pinfunction "STBY_8") (pintype "input"))
    )
    (net (code "28") (name "Net-(U501-MS_CAN_RX{slash}GP10)") (class "Default")
      (node (ref "R517") (pin "1") (pinfunction "1_1") (pintype "passive"))
      (node (ref "U501") (pin "11") (pinfunction "MS_CAN_RX/GP10_11") (pintype "input"))
    )
    (net (code "29") (name "Net-(U501-MS_CAN_TX{slash}GP11)") (class "Default")
      (node (ref "R518") (pin "1") (pinfunction "1_1") (pintype "passive"))
      (node (ref "U501") (pin "9") (pinfunction "MS_CAN_TX/GP11_9") (pintype "output"))
    )
    (net (code "30") (name "Net-(U501-SW_CAN_RX{slash}GP12)") (class "Default")
      (node (ref "R519") (pin "1") (pinfunction "1_1") (pintype "passive"))
      (node (ref "U501") (pin "42") (pinfunction "SW_CAN_RX/GP12_42") (pintype "input"))
    )
    (net (code "31") (name "Net-(U501-SW_CAN_TX{slash}GP13)") (class "Default")
      (node (ref "R520") (pin "1") (pinfunction "1_1") (pintype "passive"))
      (node (ref "U501") (pin "41") (pinfunction "SW_CAN_TX/GP13_41") (pintype "output"))
    )
    (net (code "32") (name "Net-(U501-VCAP)") (class "Default")
      (node (ref "C510") (pin "1") (pinfunction "1_1") (pintype "passive"))
      (node (ref "U501") (pin "7") (pinfunction "VCAP_7") (pintype "passive"))
    )
    (net (code "33") (name "Net-(X500-X1)") (class "Default")
      (node (ref "C511") (pin "2") (pinfunction "2_2") (pintype "passive"))
      (node (ref "R514") (pin "2") (pinfunction "2_2") (pintype "passive"))
      (node (ref "X500") (pin "1") (pinfunction "X1_1") (pintype "passive"))
    )
    (net (code "34") (name "unconnected-(SW500-Pad1')") (class "Default")
      (node (ref "SW500") (pin "1'") (pinfunction "1'_1'") (pintype "passive"))
    )
    (net (code "35") (name "unconnected-(U501-ISO_K_TX{slash}GP6-Pad43)") (class "Default")
      (node (ref "U501") (pin "43") (pinfunction "ISO_K_TX/GP6_43") (pintype "output"))
    )
    (net (code "36") (name "unconnected-(U501-ISO_L_TX{slash}GP7-Pad44)") (class "Default")
      (node (ref "U501") (pin "44") (pinfunction "ISO_L_TX/GP7_44") (pintype "output"))
    )
    (net (code "37") (name "unconnected-(U501-J1850_BUS+_TX{slash}GP2-Pad24)") (class "Default")
      (node (ref "U501") (pin "24") (pinfunction "J1850_BUS+_TX/GP2_24") (pintype "output"))
    )
    (net (code "38") (name "unconnected-(U501-J1850_BUS+_VH{slash}GP4-Pad25)") (class "Default")
      (node (ref "U501") (pin "25") (pinfunction "J1850_BUS+_VH/GP4_25") (pintype "output"))
    )
    (net (code "39") (name "unconnected-(U501-J1850_BUS_TX{slash}GP3-Pad33)") (class "Default")
      (node (ref "U501") (pin "33") (pinfunction "J1850_BUS_TX/GP3_33") (pintype "output"))
    )
    (net (code "40") (name "unconnected-(U501-SW_CAN_LOAD{slash}GP16-Pad34)") (class "Default")
      (node (ref "U501") (pin "34") (pinfunction "SW_CAN_LOAD/GP16_34") (pintype "output"))
    )
    (net (code "41") (name "unconnected-(U501-SW_CAN_MODE0{slash}GP14-Pad35)") (class "Default")
      (node (ref "U501") (pin "35") (pinfunction "SW_CAN_MODE0/GP14_35") (pintype "output"))
    )
    (net (code "42") (name "unconnected-(U501-SW_CAN_MODE1{slash}GP15-Pad36)") (class "Default")
      (node (ref "U501") (pin "36") (pinfunction "SW_CAN_MODE1/GP15_36") (pintype "output"))
    )
    (net (code "43") (name "unconnected-(X501-J1850+-Pad2)") (class "Default")
      (node (ref "X501") (pin "2") (pinfunction "J1850+_2") (pintype "passive"))
    )
    (net (code "44") (name "unconnected-(X501-J1850--Pad10)") (class "Default")
      (node (ref "X501") (pin "10") (pinfunction "J1850-_10") (pintype "passive"))
    )
    (net (code "45") (name "unconnected-(X501-K-Pad7)") (class "Default")
      (node (ref "X501") (pin "7") (pinfunction "K_7") (pintype "passive"))
    )
    (net (code "46") (name "unconnected-(X501-L-Pad15)") (class "Default")
      (node (ref "X501") (pin "15") (pinfunction "L_15") (pintype "passive"))
    )
    (net (code "47") (name "unconnected-(X501-VO-Pad1)") (class "Default")
      (node (ref "X501") (pin "1") (pinfunction "VO_1") (pintype "passive"))
    )
    (net (code "48") (name "unconnected-(X501-VO-Pad3)") (class "Default")
      (node (ref "X501") (pin "3") (pinfunction "VO_3") (pintype "passive"))
    )
    (net (code "49") (name "unconnected-(X501-VO-Pad8)") (class "Default")
      (node (ref "X501") (pin "8") (pinfunction "VO_8") (pintype "passive"))
    )
    (net (code "50") (name "unconnected-(X501-VO-Pad9)") (class "Default")
      (node (ref "X501") (pin "9") (pinfunction "VO_9") (pintype "passive"))
    )
    (net (code "51") (name "unconnected-(X501-VO-Pad11)") (class "Default")
      (node (ref "X501") (pin "11") (pinfunction "VO_11") (pintype "passive"))
    )
    (net (code "52") (name "unconnected-(X501-VO-Pad12)") (class "Default")
      (node (ref "X501") (pin "12") (pinfunction "VO_12") (pintype "passive"))
    )
    (net (code "53") (name "unconnected-(X501-VO-Pad13)") (class "Default")
      (node (ref "X501") (pin "13") (pinfunction "VO_13") (pintype "passive"))
    )
  )
)
